# PCB_mezzanine_analog_template.net
KiCad netlist of a schematic drawn in Altium Designer
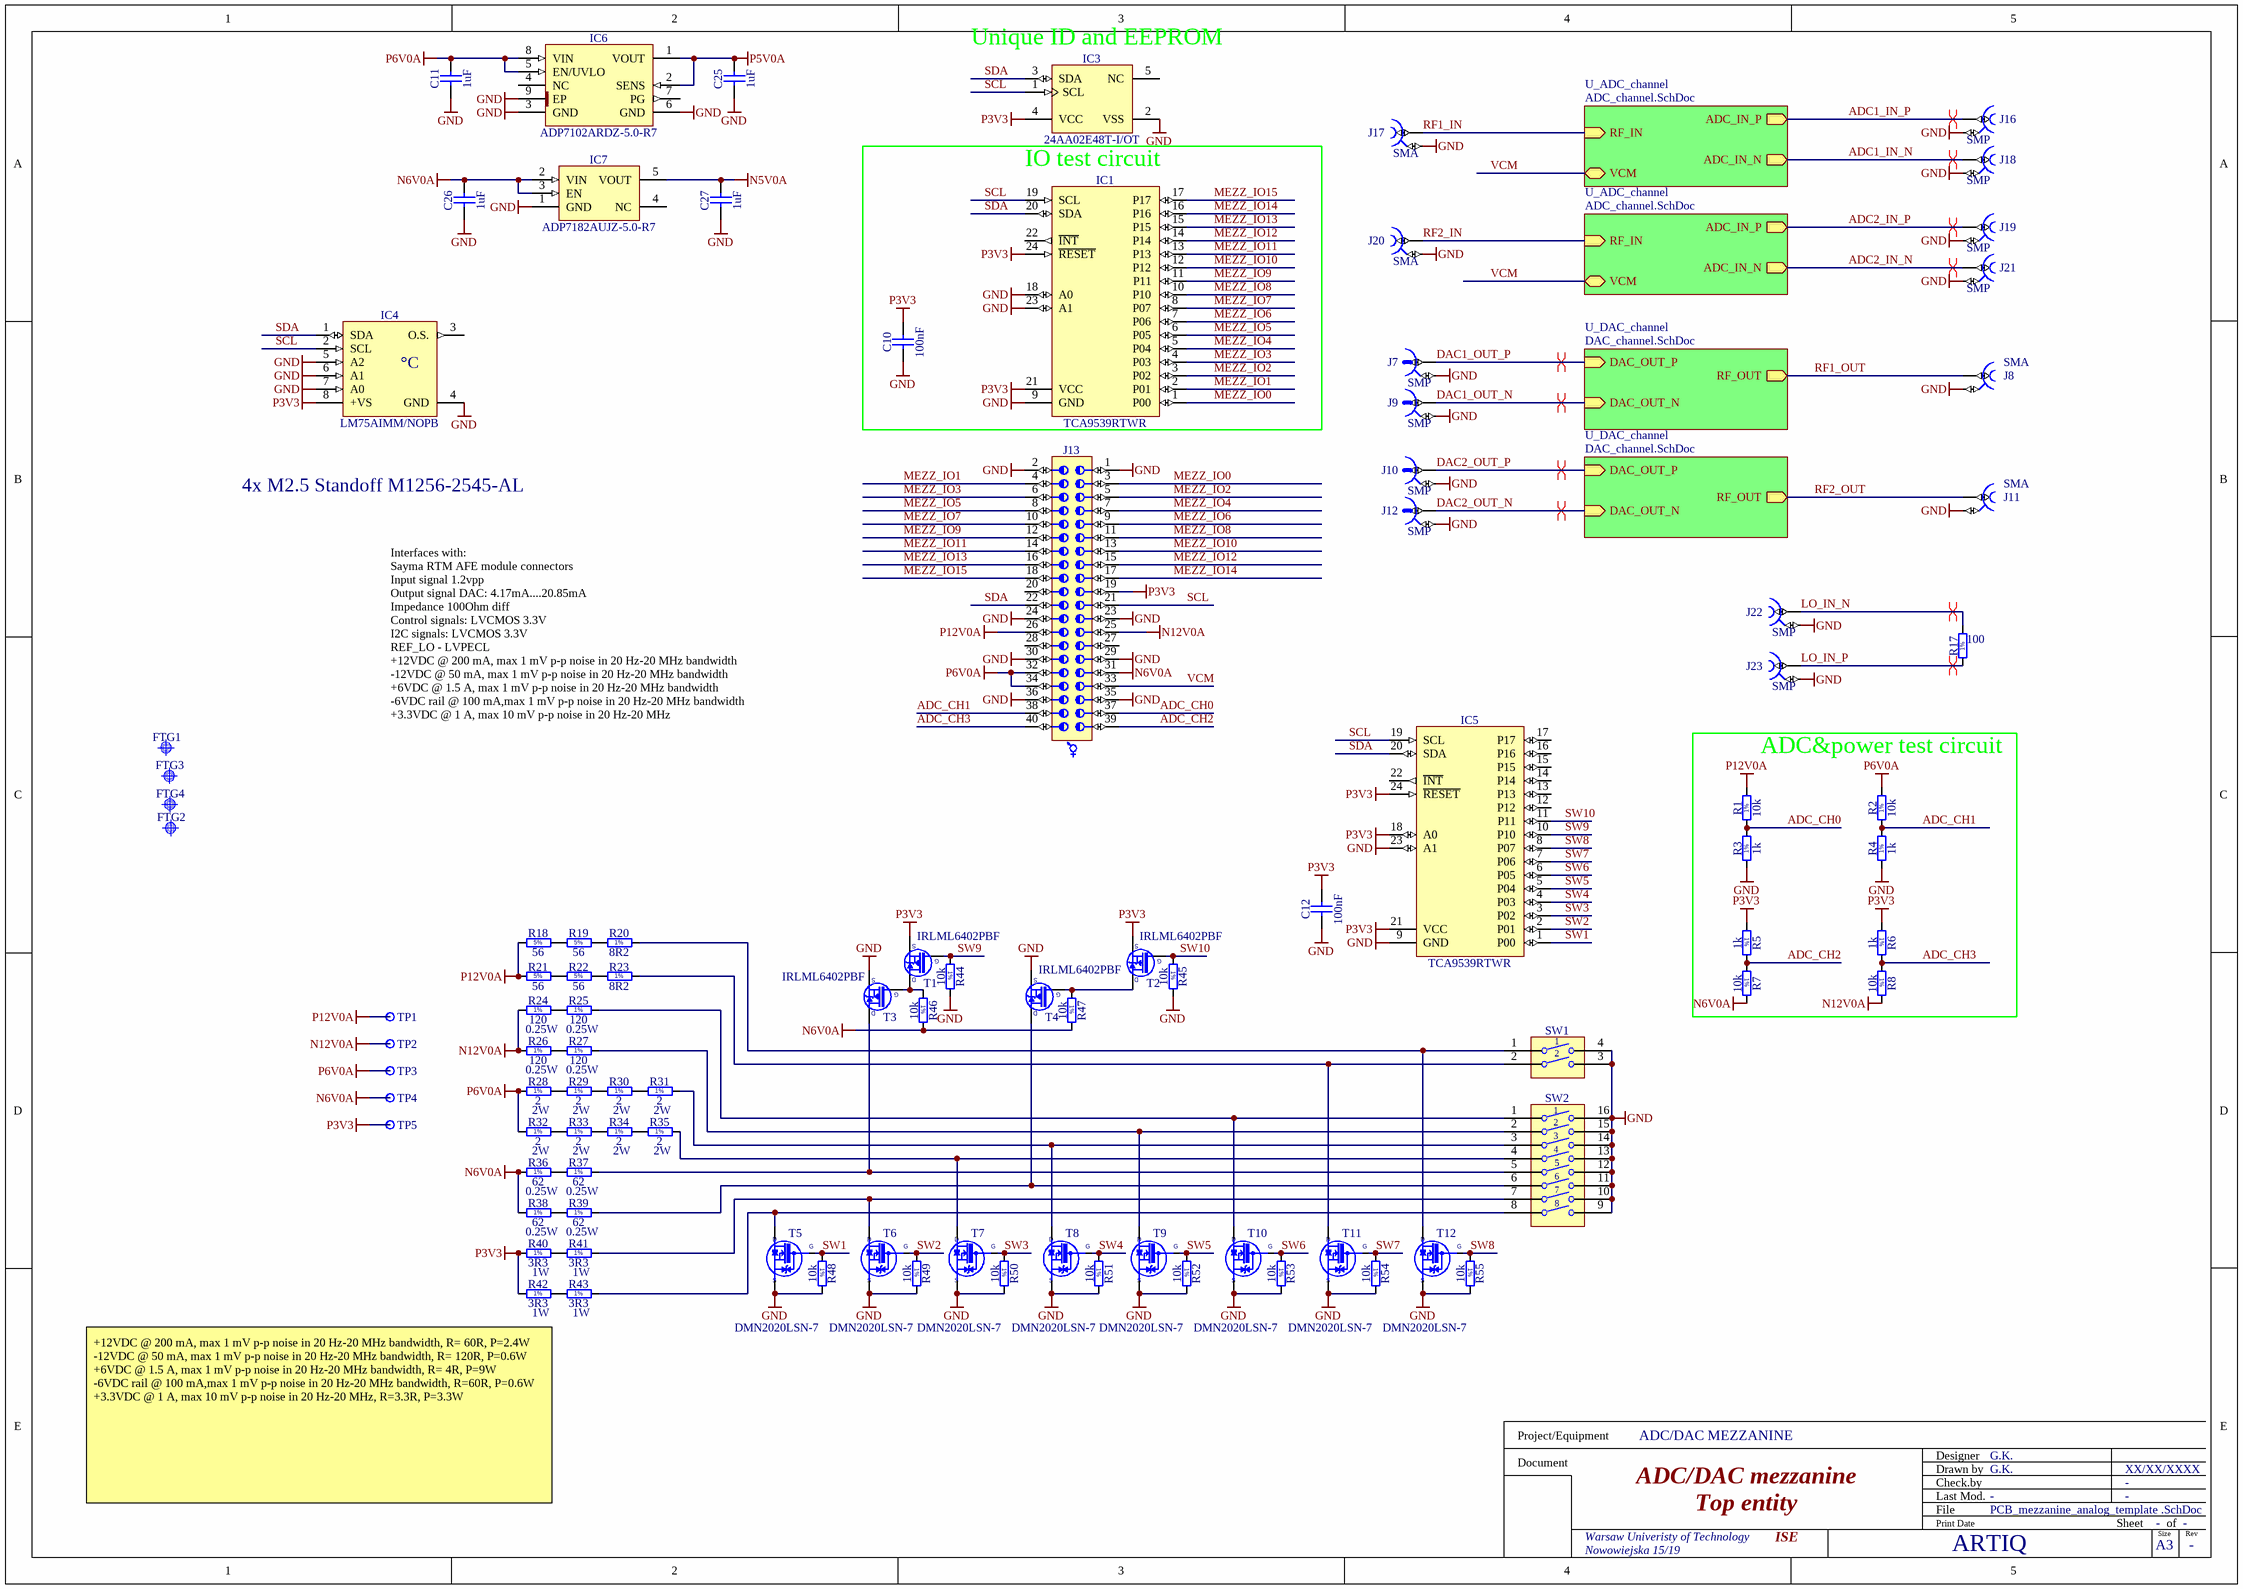
[diagram p0: PCB_mezzanine_analog_template .SchDoc]

(export (version "E")
  (design (tool "Eeschema 10.0.6"))
  (components
    (comp (ref "C10")
      (value "100nF")
      (footprint "CAPC1005X55N")
      (description "Non-polarised capacitor")
      (fields
        (field (name "PART NUMBER") "CC0402_100NF_16V_10%_X5R")
        (field (name "VOLTAGE") "16V")
        (field (name "AUTHOR") "CERN DEM JLC")
      )
      (libsource (lib "Capacitors") (part "Capacitor - non polarized"))
    )
    (comp (ref "C11")
      (value "1uF")
      (footprint "CAPC2012X140N")
      (description "Non-polarised capacitor")
      (fields
        (field (name "PART NUMBER") "CC0805_1UF_35V_20%_X7R")
        (field (name "VOLTAGE") "35V")
        (field (name "AUTHOR") "CERN DEM JLC")
      )
      (libsource (lib "Capacitors") (part "Capacitor - non polarized"))
    )
    (comp (ref "C12")
      (value "100nF")
      (footprint "CAPC1005X55N")
      (description "Non-polarised capacitor")
      (fields
        (field (name "PART NUMBER") "CC0402_100NF_16V_10%_X5R")
        (field (name "VOLTAGE") "16V")
        (field (name "AUTHOR") "CERN DEM JLC")
      )
      (libsource (lib "Capacitors") (part "Capacitor - non polarized"))
    )
    (comp (ref "C25")
      (value "1uF")
      (footprint "CAPC2012X140N")
      (description "Non-polarised capacitor")
      (fields
        (field (name "PART NUMBER") "CC0805_1UF_35V_20%_X7R")
        (field (name "VOLTAGE") "35V")
        (field (name "AUTHOR") "CERN DEM JLC")
      )
      (libsource (lib "Capacitors") (part "Capacitor - non polarized"))
    )
    (comp (ref "C26")
      (value "1uF")
      (footprint "CAPC2012X140N")
      (description "Non-polarised capacitor")
      (fields
        (field (name "PART NUMBER") "CC0805_1UF_35V_20%_X7R")
        (field (name "VOLTAGE") "35V")
        (field (name "AUTHOR") "CERN DEM JLC")
      )
      (libsource (lib "Capacitors") (part "Capacitor - non polarized"))
    )
    (comp (ref "C27")
      (value "1uF")
      (footprint "CAPC2012X140N")
      (description "Non-polarised capacitor")
      (fields
        (field (name "PART NUMBER") "CC0805_1UF_35V_20%_X7R")
        (field (name "VOLTAGE") "35V")
        (field (name "AUTHOR") "CERN DEM JLC")
      )
      (libsource (lib "Capacitors") (part "Capacitor - non polarized"))
    )
    (comp (ref "FTG1")
      (value "Use only in PCB")
      (footprint "FIDUCIAL_TOP_C100-200")
      (description "Fiducial Target")
      (fields (field (name "PART NUMBER") "FIDUCIAL_TARGET_C100-200") (field (name "AUTHOR") "CERN DEM JLC"))
      (libsource (lib "Eletro-mechanical") (part "Fiducial Target"))
    )
    (comp (ref "FTG2")
      (value "Use only in PCB")
      (footprint "FIDUCIAL_TOP_S100-200")
      (description "Fiducial Target")
      (fields (field (name "PART NUMBER") "FIDUCIAL_TARGET_S100-200") (field (name "AUTHOR") "CERN DEM JLC"))
      (libsource (lib "Eletro-mechanical") (part "Fiducial Target"))
    )
    (comp (ref "FTG3")
      (value "Use only in PCB")
      (footprint "FIDUCIAL_TOP_S100-200")
      (description "Fiducial Target")
      (fields (field (name "PART NUMBER") "FIDUCIAL_TARGET_S100-200") (field (name "AUTHOR") "CERN DEM JLC"))
      (libsource (lib "Eletro-mechanical") (part "Fiducial Target"))
    )
    (comp (ref "FTG4")
      (value "Use only in PCB")
      (footprint "FIDUCIAL_TOP_S200-400")
      (description "Fiducial Target")
      (fields (field (name "PART NUMBER") "FIDUCIAL_TARGET_S200-400") (field (name "AUTHOR") "CERN DEM JLC"))
      (libsource (lib "Eletro-mechanical") (part "Fiducial Target"))
    )
    (comp (ref "IC1")
      (value "TCA9539RTWR")
      (footprint "QFN50P400X400X80-25N-S255")
      (description "Low-Voltage 16-Bit I2C and SMBus I/O Expander")
      (fields (field (name "MANUFACTURER") "TEXAS INSTRUMENTS") (field (name "AUTHOR") "CERN DEM MR"))
      (libsource (lib "ICs And Semiconductors") (part "TCA9539RTWR"))
    )
    (comp (ref "IC3")
      (value "24AA02E48T-I/OT")
      (footprint "SOT95P280X145-5N")
      (description "1.7V-5.5V, 2K I2C Serial EEPROM With EUI-48 Node Identity")
      (fields (field (name "MANUFACTURER") "MICROCHIP TECHNOLOGY") (field (name "AUTHOR") "CERN DEM MR"))
      (libsource (lib "ICs And Semiconductors") (part "24AA02E48T-I/OT"))
    )
    (comp (ref "IC4")
      (value "LM75AIMM/NOPB")
      (footprint "SOP65P490X109-8N")
      (description "Digital Temperature Sensor and Thermal Watchdog with Two-Wire Interface")
      (fields (field (name "MANUFACTURER") "TEXAS INSTRUMENTS") (field (name "AUTHOR") "CERN DEM JLC"))
      (libsource (lib "ICs And Semiconductors") (part "LM75"))
    )
    (comp (ref "IC5")
      (value "TCA9539RTWR")
      (footprint "QFN50P400X400X80-25N-S255")
      (description "Low-Voltage 16-Bit I2C and SMBus I/O Expander")
      (fields (field (name "MANUFACTURER") "TEXAS INSTRUMENTS") (field (name "AUTHOR") "CERN DEM MR"))
      (libsource (lib "ICs And Semiconductors") (part "TCA9539RTWR"))
    )
    (comp (ref "IC6")
      (value "ADP7102ARDZ-5.0-R7")
      (footprint "SOIC127P600X175-9N-R241X309")
      (description "300 mA, Low Noise, CMOS LDO Linear Regulator")
      (fields (field (name "MANUFACTURER") "ANALOG DEVICES") (field (name "AUTHOR") "CERN DEM JLC"))
      (libsource (lib "ICs And Semiconductors") (part "ADP7102ARDZ-X.X-R7"))
    )
    (comp (ref "IC7")
      (value "ADP7182AUJZ-5.0-R7")
      (footprint "SOT95P280X90-5N")
      (description "–5V, 200 mA, Low Noise, Linear Regulator")
      (fields (field (name "MANUFACTURER") "ANALOG DEVICES") (field (name "AUTHOR") "CERN DEM JLC"))
      (libsource (lib "ICs And Semiconductors") (part "ADP7182AUJZ-X.X-R7"))
    )
    (comp (ref "J7")
      (value "SMP")
      (footprint "MOLEX_85305-0232")
      (fields
        (field (name "PART NUMBER") "MOLEX_85305-0232")
        (field (name "MANUFACTURER") "MOLEX")
        (field (name "MANUFACTURER PART NUMBER") "85305-0232")
        (field (name "AUTHOR") "CERN DEM JMW")
      )
      (libsource (lib "Connectors") (part "Coax_1Male_1Shield"))
    )
    (comp (ref "J8")
      (value "SMA")
      (footprint "TELEGARTNER_J01151A0451")
      (fields
        (field (name "PART NUMBER") "TELEGARTNER_J01151A0451")
        (field (name "MANUFACTURER") "TELEGARTNER")
        (field (name "MANUFACTURER PART NUMBER") "J01151A0451")
        (field (name "AUTHOR") "CERN DEM JLC")
      )
      (libsource (lib "") (part "Coax_1Female_1Shield_1"))
    )
    (comp (ref "J9")
      (value "SMP")
      (footprint "MOLEX_85305-0232")
      (fields
        (field (name "PART NUMBER") "MOLEX_85305-0232")
        (field (name "MANUFACTURER") "MOLEX")
        (field (name "MANUFACTURER PART NUMBER") "85305-0232")
        (field (name "AUTHOR") "CERN DEM JMW")
      )
      (libsource (lib "Connectors") (part "Coax_1Male_1Shield"))
    )
    (comp (ref "J10")
      (value "SMP")
      (footprint "MOLEX_85305-0232")
      (fields
        (field (name "PART NUMBER") "MOLEX_85305-0232")
        (field (name "MANUFACTURER") "MOLEX")
        (field (name "MANUFACTURER PART NUMBER") "85305-0232")
        (field (name "AUTHOR") "CERN DEM JMW")
      )
      (libsource (lib "Connectors") (part "Coax_1Male_1Shield"))
    )
    (comp (ref "J11")
      (value "SMA")
      (footprint "TELEGARTNER_J01151A0451")
      (fields
        (field (name "PART NUMBER") "TELEGARTNER_J01151A0451")
        (field (name "MANUFACTURER") "TELEGARTNER")
        (field (name "MANUFACTURER PART NUMBER") "J01151A0451")
        (field (name "AUTHOR") "CERN DEM JLC")
      )
      (libsource (lib "") (part "Coax_1Female_1Shield_1"))
    )
    (comp (ref "J12")
      (value "SMP")
      (footprint "MOLEX_85305-0232")
      (fields
        (field (name "PART NUMBER") "MOLEX_85305-0232")
        (field (name "MANUFACTURER") "MOLEX")
        (field (name "MANUFACTURER PART NUMBER") "85305-0232")
        (field (name "AUTHOR") "CERN DEM JMW")
      )
      (libsource (lib "Connectors") (part "Coax_1Male_1Shield"))
    )
    (comp (ref "J13")
      (value "~")
      (footprint "SAMTEC_LSS-120-03-L-DV-A")
      (description "Connector 40 Hermaphroditic")
      (fields
        (field (name "PART NUMBER") "SAMTEC_LSS-120-03-L-DV-A")
        (field (name "MANUFACTURER") "SAMTEC")
        (field (name "AUTHOR") "CERN DEM JMW")
      )
      (libsource (lib "Connectors") (part "Connector 40 Hermaphroditic"))
    )
    (comp (ref "J16")
      (value "SMP")
      (footprint "AMPHENOL_SMP-MSLD-PCT-10")
      (fields
        (field (name "PART NUMBER") "AMPHENOL_SMP-MSLD-PCT-10")
        (field (name "MANUFACTURER") "AMPHENOL")
        (field (name "MANUFACTURER PART NUMBER") "SMP-MSLD-PCT-10")
        (field (name "AUTHOR") "CERN DEM JLC")
      )
      (libsource (lib "") (part "Coax_1Female_1Shield_1"))
    )
    (comp (ref "J17")
      (value "SMA")
      (footprint "TELEGARTNER_J01151A0921")
      (fields
        (field (name "PART NUMBER") "TELEGARTNER_J01151A0921")
        (field (name "MANUFACTURER") "TELEGARTNER")
        (field (name "MANUFACTURER PART NUMBER") "J01151A0921")
        (field (name "AUTHOR") "CERN DEM JLC")
      )
      (libsource (lib "Connectors") (part "Coax_1Female_1Shield"))
    )
    (comp (ref "J18")
      (value "SMP")
      (footprint "AMPHENOL_SMP-MSLD-PCT-10")
      (fields
        (field (name "PART NUMBER") "AMPHENOL_SMP-MSLD-PCT-10")
        (field (name "MANUFACTURER") "AMPHENOL")
        (field (name "MANUFACTURER PART NUMBER") "SMP-MSLD-PCT-10")
        (field (name "AUTHOR") "CERN DEM JLC")
      )
      (libsource (lib "") (part "Coax_1Female_1Shield_1"))
    )
    (comp (ref "J19")
      (value "SMP")
      (footprint "AMPHENOL_SMP-MSLD-PCT-10")
      (fields
        (field (name "PART NUMBER") "AMPHENOL_SMP-MSLD-PCT-10")
        (field (name "MANUFACTURER") "AMPHENOL")
        (field (name "MANUFACTURER PART NUMBER") "SMP-MSLD-PCT-10")
        (field (name "AUTHOR") "CERN DEM JLC")
      )
      (libsource (lib "") (part "Coax_1Female_1Shield_1"))
    )
    (comp (ref "J20")
      (value "SMA")
      (footprint "TELEGARTNER_J01151A0921")
      (fields
        (field (name "PART NUMBER") "TELEGARTNER_J01151A0921")
        (field (name "MANUFACTURER") "TELEGARTNER")
        (field (name "MANUFACTURER PART NUMBER") "J01151A0921")
        (field (name "AUTHOR") "CERN DEM JLC")
      )
      (libsource (lib "Connectors") (part "Coax_1Female_1Shield"))
    )
    (comp (ref "J21")
      (value "SMP")
      (footprint "AMPHENOL_SMP-MSLD-PCT-10")
      (fields
        (field (name "PART NUMBER") "AMPHENOL_SMP-MSLD-PCT-10")
        (field (name "MANUFACTURER") "AMPHENOL")
        (field (name "MANUFACTURER PART NUMBER") "SMP-MSLD-PCT-10")
        (field (name "AUTHOR") "CERN DEM JLC")
      )
      (libsource (lib "") (part "Coax_1Female_1Shield_1"))
    )
    (comp (ref "J22")
      (value "SMP")
      (footprint "AMPHENOL_SMP-MSLD-PCT-10")
      (fields
        (field (name "PART NUMBER") "AMPHENOL_SMP-MSLD-PCT-10")
        (field (name "MANUFACTURER") "AMPHENOL")
        (field (name "MANUFACTURER PART NUMBER") "SMP-MSLD-PCT-10")
        (field (name "AUTHOR") "CERN DEM JLC")
      )
      (libsource (lib "Connectors") (part "Coax_1Female_1Shield"))
    )
    (comp (ref "J23")
      (value "SMP")
      (footprint "AMPHENOL_SMP-MSLD-PCT-10")
      (fields
        (field (name "PART NUMBER") "AMPHENOL_SMP-MSLD-PCT-10")
        (field (name "MANUFACTURER") "AMPHENOL")
        (field (name "MANUFACTURER PART NUMBER") "SMP-MSLD-PCT-10")
        (field (name "AUTHOR") "CERN DEM JLC")
      )
      (libsource (lib "Connectors") (part "Coax_1Female_1Shield"))
    )
    (comp (ref "R1")
      (value "10k")
      (footprint "RESC1005X40N")
      (description "Resistor - 1%")
      (fields
        (field (name "PART NUMBER") "R0402_10K_1%_0.0625W_100PPM")
        (field (name "POWER") "0.0625W")
        (field (name "AUTHOR") "CERN DEM JLC")
      )
      (libsource (lib "Resistors") (part "Resistor - 1%"))
    )
    (comp (ref "R2")
      (value "10k")
      (footprint "RESC1005X40N")
      (description "Resistor - 1%")
      (fields
        (field (name "PART NUMBER") "R0402_10K_1%_0.0625W_100PPM")
        (field (name "POWER") "0.0625W")
        (field (name "AUTHOR") "CERN DEM JLC")
      )
      (libsource (lib "Resistors") (part "Resistor - 1%"))
    )
    (comp (ref "R3")
      (value "1k")
      (footprint "RESC1005X40N")
      (description "Resistor - 1%")
      (fields
        (field (name "PART NUMBER") "R0402_1K_1%_0.0625W_100PPM")
        (field (name "POWER") "0.0625W")
        (field (name "AUTHOR") "CERN DEM JLC")
      )
      (libsource (lib "Resistors") (part "Resistor - 1%"))
    )
    (comp (ref "R4")
      (value "1k")
      (footprint "RESC1005X40N")
      (description "Resistor - 1%")
      (fields
        (field (name "PART NUMBER") "R0402_1K_1%_0.0625W_100PPM")
        (field (name "POWER") "0.0625W")
        (field (name "AUTHOR") "CERN DEM JLC")
      )
      (libsource (lib "Resistors") (part "Resistor - 1%"))
    )
    (comp (ref "R5")
      (value "1k")
      (footprint "RESC1005X40N")
      (description "Resistor - 1%")
      (fields
        (field (name "PART NUMBER") "R0402_1K_1%_0.0625W_100PPM")
        (field (name "POWER") "0.0625W")
        (field (name "AUTHOR") "CERN DEM JLC")
      )
      (libsource (lib "Resistors") (part "Resistor - 1%"))
    )
    (comp (ref "R6")
      (value "1k")
      (footprint "RESC1005X40N")
      (description "Resistor - 1%")
      (fields
        (field (name "PART NUMBER") "R0402_1K_1%_0.0625W_100PPM")
        (field (name "POWER") "0.0625W")
        (field (name "AUTHOR") "CERN DEM JLC")
      )
      (libsource (lib "Resistors") (part "Resistor - 1%"))
    )
    (comp (ref "R7")
      (value "10k")
      (footprint "RESC1005X40N")
      (description "Resistor - 1%")
      (fields
        (field (name "PART NUMBER") "R0402_10K_1%_0.0625W_100PPM")
        (field (name "POWER") "0.0625W")
        (field (name "AUTHOR") "CERN DEM JLC")
      )
      (libsource (lib "Resistors") (part "Resistor - 1%"))
    )
    (comp (ref "R8")
      (value "10k")
      (footprint "RESC1005X40N")
      (description "Resistor - 1%")
      (fields
        (field (name "PART NUMBER") "R0402_10K_1%_0.0625W_100PPM")
        (field (name "POWER") "0.0625W")
        (field (name "AUTHOR") "CERN DEM JLC")
      )
      (libsource (lib "Resistors") (part "Resistor - 1%"))
    )
    (comp (ref "R17")
      (value "100")
      (footprint "RESC1005X40N")
      (description "Resistor - 1%")
      (fields
        (field (name "PART NUMBER") "R0402_100R_1%_0.0625W_100PPM")
        (field (name "POWER") "0.0625W")
        (field (name "AUTHOR") "CERN DEM JLC")
      )
      (libsource (lib "Resistors") (part "Resistor - 1%"))
    )
    (comp (ref "R18")
      (value "56")
      (footprint "RESC6331X70N")
      (description "Resistor - 5%")
      (fields
        (field (name "PART NUMBER") "R2512_56R_5%_1W_200PPM")
        (field (name "POWER") "1W")
        (field (name "AUTHOR") "CERN DEM JLC")
      )
      (libsource (lib "Resistors") (part "Resistor - 5%"))
    )
    (comp (ref "R19")
      (value "56")
      (footprint "RESC6331X70N")
      (description "Resistor - 5%")
      (fields
        (field (name "PART NUMBER") "R2512_56R_5%_1W_200PPM")
        (field (name "POWER") "1W")
        (field (name "AUTHOR") "CERN DEM JLC")
      )
      (libsource (lib "Resistors") (part "Resistor - 5%"))
    )
    (comp (ref "R20")
      (value "8R2")
      (footprint "RESC3216X65N")
      (description "Resistor - 1%")
      (fields
        (field (name "PART NUMBER") "R1206_8R2_1%_0.25W_200PPM")
        (field (name "POWER") "0.25W")
        (field (name "AUTHOR") "CERN DEM JLC")
      )
      (libsource (lib "Resistors") (part "Resistor - 1%"))
    )
    (comp (ref "R21")
      (value "56")
      (footprint "RESC6331X70N")
      (description "Resistor - 5%")
      (fields
        (field (name "PART NUMBER") "R2512_56R_5%_1W_200PPM")
        (field (name "POWER") "1W")
        (field (name "AUTHOR") "CERN DEM JLC")
      )
      (libsource (lib "Resistors") (part "Resistor - 5%"))
    )
    (comp (ref "R22")
      (value "56")
      (footprint "RESC6331X70N")
      (description "Resistor - 5%")
      (fields
        (field (name "PART NUMBER") "R2512_56R_5%_1W_200PPM")
        (field (name "POWER") "1W")
        (field (name "AUTHOR") "CERN DEM JLC")
      )
      (libsource (lib "Resistors") (part "Resistor - 5%"))
    )
    (comp (ref "R23")
      (value "8R2")
      (footprint "RESC3216X65N")
      (description "Resistor - 1%")
      (fields
        (field (name "PART NUMBER") "R1206_8R2_1%_0.25W_200PPM")
        (field (name "POWER") "0.25W")
        (field (name "AUTHOR") "CERN DEM JLC")
      )
      (libsource (lib "Resistors") (part "Resistor - 1%"))
    )
    (comp (ref "R24")
      (value "120")
      (footprint "RESC3216X65N")
      (description "Resistor - 1%")
      (fields
        (field (name "PART NUMBER") "R1206_120R_1%_0.25W_100PPM")
        (field (name "POWER") "0.25W")
        (field (name "TOLERANCE") "±1%")
        (field (name "AUTHOR") "CERN DEM JLC")
      )
      (libsource (lib "Resistors") (part "Resistor - 1%"))
    )
    (comp (ref "R25")
      (value "120")
      (footprint "RESC3216X65N")
      (description "Resistor - 1%")
      (fields
        (field (name "PART NUMBER") "R1206_120R_1%_0.25W_100PPM")
        (field (name "POWER") "0.25W")
        (field (name "TOLERANCE") "±1%")
        (field (name "AUTHOR") "CERN DEM JLC")
      )
      (libsource (lib "Resistors") (part "Resistor - 1%"))
    )
    (comp (ref "R26")
      (value "120")
      (footprint "RESC3216X65N")
      (description "Resistor - 1%")
      (fields
        (field (name "PART NUMBER") "R1206_120R_1%_0.25W_100PPM")
        (field (name "POWER") "0.25W")
        (field (name "TOLERANCE") "±1%")
        (field (name "AUTHOR") "CERN DEM JLC")
      )
      (libsource (lib "Resistors") (part "Resistor - 1%"))
    )
    (comp (ref "R27")
      (value "120")
      (footprint "RESC3216X65N")
      (description "Resistor - 1%")
      (fields
        (field (name "PART NUMBER") "R1206_120R_1%_0.25W_100PPM")
        (field (name "POWER") "0.25W")
        (field (name "TOLERANCE") "±1%")
        (field (name "AUTHOR") "CERN DEM JLC")
      )
      (libsource (lib "Resistors") (part "Resistor - 1%"))
    )
    (comp (ref "R28")
      (value "2")
      (footprint "RESM11670X449N")
      (description "Resistor - 1%")
      (fields
        (field (name "PART NUMBER") "R4527_2R_1%_2W_50PPM")
        (field (name "POWER") "2W")
        (field (name "TOLERANCE") "±1%")
        (field (name "AUTHOR") "CERN DEM JLC")
      )
      (libsource (lib "Resistors") (part "Resistor - 1%"))
    )
    (comp (ref "R29")
      (value "2")
      (footprint "RESM11670X449N")
      (description "Resistor - 1%")
      (fields
        (field (name "PART NUMBER") "R4527_2R_1%_2W_50PPM")
        (field (name "POWER") "2W")
        (field (name "TOLERANCE") "±1%")
        (field (name "AUTHOR") "CERN DEM JLC")
      )
      (libsource (lib "Resistors") (part "Resistor - 1%"))
    )
    (comp (ref "R30")
      (value "2")
      (footprint "RESM11670X449N")
      (description "Resistor - 1%")
      (fields
        (field (name "PART NUMBER") "R4527_2R_1%_2W_50PPM")
        (field (name "POWER") "2W")
        (field (name "TOLERANCE") "±1%")
        (field (name "AUTHOR") "CERN DEM JLC")
      )
      (libsource (lib "Resistors") (part "Resistor - 1%"))
    )
    (comp (ref "R31")
      (value "2")
      (footprint "RESM11670X449N")
      (description "Resistor - 1%")
      (fields
        (field (name "PART NUMBER") "R4527_2R_1%_2W_50PPM")
        (field (name "POWER") "2W")
        (field (name "TOLERANCE") "±1%")
        (field (name "AUTHOR") "CERN DEM JLC")
      )
      (libsource (lib "Resistors") (part "Resistor - 1%"))
    )
    (comp (ref "R32")
      (value "2")
      (footprint "RESM11670X449N")
      (description "Resistor - 1%")
      (fields
        (field (name "PART NUMBER") "R4527_2R_1%_2W_50PPM")
        (field (name "POWER") "2W")
        (field (name "TOLERANCE") "±1%")
        (field (name "AUTHOR") "CERN DEM JLC")
      )
      (libsource (lib "Resistors") (part "Resistor - 1%"))
    )
    (comp (ref "R33")
      (value "2")
      (footprint "RESM11670X449N")
      (description "Resistor - 1%")
      (fields
        (field (name "PART NUMBER") "R4527_2R_1%_2W_50PPM")
        (field (name "POWER") "2W")
        (field (name "TOLERANCE") "±1%")
        (field (name "AUTHOR") "CERN DEM JLC")
      )
      (libsource (lib "Resistors") (part "Resistor - 1%"))
    )
    (comp (ref "R34")
      (value "2")
      (footprint "RESM11670X449N")
      (description "Resistor - 1%")
      (fields
        (field (name "PART NUMBER") "R4527_2R_1%_2W_50PPM")
        (field (name "POWER") "2W")
        (field (name "TOLERANCE") "±1%")
        (field (name "AUTHOR") "CERN DEM JLC")
      )
      (libsource (lib "Resistors") (part "Resistor - 1%"))
    )
    (comp (ref "R35")
      (value "2")
      (footprint "RESM11670X449N")
      (description "Resistor - 1%")
      (fields
        (field (name "PART NUMBER") "R4527_2R_1%_2W_50PPM")
        (field (name "POWER") "2W")
        (field (name "TOLERANCE") "±1%")
        (field (name "AUTHOR") "CERN DEM JLC")
      )
      (libsource (lib "Resistors") (part "Resistor - 1%"))
    )
    (comp (ref "R36")
      (value "62")
      (footprint "RESC3216X65N")
      (description "Resistor - 1%")
      (fields
        (field (name "PART NUMBER") "R1206_62R_1%_0.25W_100PPM")
        (field (name "POWER") "0.25W")
        (field (name "TOLERANCE") "±1%")
        (field (name "AUTHOR") "CERN DEM JLC")
      )
      (libsource (lib "Resistors") (part "Resistor - 1%"))
    )
    (comp (ref "R37")
      (value "62")
      (footprint "RESC3216X65N")
      (description "Resistor - 1%")
      (fields
        (field (name "PART NUMBER") "R1206_62R_1%_0.25W_100PPM")
        (field (name "POWER") "0.25W")
        (field (name "TOLERANCE") "±1%")
        (field (name "AUTHOR") "CERN DEM JLC")
      )
      (libsource (lib "Resistors") (part "Resistor - 1%"))
    )
    (comp (ref "R38")
      (value "62")
      (footprint "RESC3216X65N")
      (description "Resistor - 1%")
      (fields
        (field (name "PART NUMBER") "R1206_62R_1%_0.25W_100PPM")
        (field (name "POWER") "0.25W")
        (field (name "TOLERANCE") "±1%")
        (field (name "AUTHOR") "CERN DEM JLC")
      )
      (libsource (lib "Resistors") (part "Resistor - 1%"))
    )
    (comp (ref "R39")
      (value "62")
      (footprint "RESC3216X65N")
      (description "Resistor - 1%")
      (fields
        (field (name "PART NUMBER") "R1206_62R_1%_0.25W_100PPM")
        (field (name "POWER") "0.25W")
        (field (name "TOLERANCE") "±1%")
        (field (name "AUTHOR") "CERN DEM JLC")
      )
      (libsource (lib "Resistors") (part "Resistor - 1%"))
    )
    (comp (ref "R40")
      (value "3R3")
      (footprint "RESC6331X70N")
      (description "Resistor - 1%")
      (fields
        (field (name "PART NUMBER") "R2512_3R3_1%_1W_200PPM")
        (field (name "POWER") "1W")
        (field (name "TOLERANCE") "±1%")
        (field (name "AUTHOR") "CERN DEM JLC")
      )
      (libsource (lib "Resistors") (part "Resistor - 1%"))
    )
    (comp (ref "R41")
      (value "3R3")
      (footprint "RESC6331X70N")
      (description "Resistor - 1%")
      (fields
        (field (name "PART NUMBER") "R2512_3R3_1%_1W_200PPM")
        (field (name "POWER") "1W")
        (field (name "TOLERANCE") "±1%")
        (field (name "AUTHOR") "CERN DEM JLC")
      )
      (libsource (lib "Resistors") (part "Resistor - 1%"))
    )
    (comp (ref "R42")
      (value "3R3")
      (footprint "RESC6331X70N")
      (description "Resistor - 1%")
      (fields
        (field (name "PART NUMBER") "R2512_3R3_1%_1W_200PPM")
        (field (name "POWER") "1W")
        (field (name "TOLERANCE") "±1%")
        (field (name "AUTHOR") "CERN DEM JLC")
      )
      (libsource (lib "Resistors") (part "Resistor - 1%"))
    )
    (comp (ref "R43")
      (value "3R3")
      (footprint "RESC6331X70N")
      (description "Resistor - 1%")
      (fields
        (field (name "PART NUMBER") "R2512_3R3_1%_1W_200PPM")
        (field (name "POWER") "1W")
        (field (name "TOLERANCE") "±1%")
        (field (name "AUTHOR") "CERN DEM JLC")
      )
      (libsource (lib "Resistors") (part "Resistor - 1%"))
    )
    (comp (ref "R44")
      (value "10k")
      (footprint "RESC1005X40N")
      (description "Resistor - 1%")
      (fields
        (field (name "PART NUMBER") "R0402_10K_1%_0.0625W_100PPM")
        (field (name "POWER") "0.0625W")
        (field (name "AUTHOR") "CERN DEM JLC")
      )
      (libsource (lib "Resistors") (part "Resistor - 1%"))
    )
    (comp (ref "R45")
      (value "10k")
      (footprint "RESC1005X40N")
      (description "Resistor - 1%")
      (fields
        (field (name "PART NUMBER") "R0402_10K_1%_0.0625W_100PPM")
        (field (name "POWER") "0.0625W")
        (field (name "AUTHOR") "CERN DEM JLC")
      )
      (libsource (lib "Resistors") (part "Resistor - 1%"))
    )
    (comp (ref "R46")
      (value "10k")
      (footprint "RESC1005X40N")
      (description "Resistor - 1%")
      (fields
        (field (name "PART NUMBER") "R0402_10K_1%_0.0625W_100PPM")
        (field (name "POWER") "0.0625W")
        (field (name "AUTHOR") "CERN DEM JLC")
      )
      (libsource (lib "Resistors") (part "Resistor - 1%"))
    )
    (comp (ref "R47")
      (value "10k")
      (footprint "RESC1005X40N")
      (description "Resistor - 1%")
      (fields
        (field (name "PART NUMBER") "R0402_10K_1%_0.0625W_100PPM")
        (field (name "POWER") "0.0625W")
        (field (name "AUTHOR") "CERN DEM JLC")
      )
      (libsource (lib "Resistors") (part "Resistor - 1%"))
    )
    (comp (ref "R48")
      (value "10k")
      (footprint "RESC1005X40N")
      (description "Resistor - 1%")
      (fields
        (field (name "PART NUMBER") "R0402_10K_1%_0.0625W_100PPM")
        (field (name "POWER") "0.0625W")
        (field (name "AUTHOR") "CERN DEM JLC")
      )
      (libsource (lib "Resistors") (part "Resistor - 1%"))
    )
    (comp (ref "R49")
      (value "10k")
      (footprint "RESC1005X40N")
      (description "Resistor - 1%")
      (fields
        (field (name "PART NUMBER") "R0402_10K_1%_0.0625W_100PPM")
        (field (name "POWER") "0.0625W")
        (field (name "AUTHOR") "CERN DEM JLC")
      )
      (libsource (lib "Resistors") (part "Resistor - 1%"))
    )
    (comp (ref "R50")
      (value "10k")
      (footprint "RESC1005X40N")
      (description "Resistor - 1%")
      (fields
        (field (name "PART NUMBER") "R0402_10K_1%_0.0625W_100PPM")
        (field (name "POWER") "0.0625W")
        (field (name "AUTHOR") "CERN DEM JLC")
      )
      (libsource (lib "Resistors") (part "Resistor - 1%"))
    )
    (comp (ref "R51")
      (value "10k")
      (footprint "RESC1005X40N")
      (description "Resistor - 1%")
      (fields
        (field (name "PART NUMBER") "R0402_10K_1%_0.0625W_100PPM")
        (field (name "POWER") "0.0625W")
        (field (name "AUTHOR") "CERN DEM JLC")
      )
      (libsource (lib "Resistors") (part "Resistor - 1%"))
    )
    (comp (ref "R52")
      (value "10k")
      (footprint "RESC1005X40N")
      (description "Resistor - 1%")
      (fields
        (field (name "PART NUMBER") "R0402_10K_1%_0.0625W_100PPM")
        (field (name "POWER") "0.0625W")
        (field (name "AUTHOR") "CERN DEM JLC")
      )
      (libsource (lib "Resistors") (part "Resistor - 1%"))
    )
    (comp (ref "R53")
      (value "10k")
      (footprint "RESC1005X40N")
      (description "Resistor - 1%")
      (fields
        (field (name "PART NUMBER") "R0402_10K_1%_0.0625W_100PPM")
        (field (name "POWER") "0.0625W")
        (field (name "AUTHOR") "CERN DEM JLC")
      )
      (libsource (lib "Resistors") (part "Resistor - 1%"))
    )
    (comp (ref "R54")
      (value "10k")
      (footprint "RESC1005X40N")
      (description "Resistor - 1%")
      (fields
        (field (name "PART NUMBER") "R0402_10K_1%_0.0625W_100PPM")
        (field (name "POWER") "0.0625W")
        (field (name "AUTHOR") "CERN DEM JLC")
      )
      (libsource (lib "Resistors") (part "Resistor - 1%"))
    )
    (comp (ref "R55")
      (value "10k")
      (footprint "RESC1005X40N")
      (description "Resistor - 1%")
      (fields
        (field (name "PART NUMBER") "R0402_10K_1%_0.0625W_100PPM")
        (field (name "POWER") "0.0625W")
        (field (name "AUTHOR") "CERN DEM JLC")
      )
      (libsource (lib "Resistors") (part "Resistor - 1%"))
    )
    (comp (ref "SW1")
      (value "Switch")
      (footprint "SW_OMRON_A6S-2102-H")
      (description "2 Ways SPST DIP Switch")
      (fields
        (field (name "PART NUMBER") "SW_OMRON_A6S-2102-H")
        (field (name "MANUFACTURER") "OMRON")
        (field (name "AUTHOR") "CERN DEM JMW")
      )
      (libsource (lib "Eletro-mechanical") (part "SW 2x SPST DIP Switch"))
    )
    (comp (ref "SW2")
      (value "Switch")
      (footprint "SW_OMRON_A6S-8102-H")
      (description "8 Ways SPST DIP Switch")
      (fields
        (field (name "PART NUMBER") "SW_OMRON_A6S-8102-H")
        (field (name "MANUFACTURER") "OMRON")
        (field (name "AUTHOR") "CERN DEM JMW")
      )
      (libsource (lib "Eletro-mechanical") (part "SW 8x SPST DIP Switch"))
    )
    (comp (ref "T1")
      (value "IRLML6402PBF")
      (footprint "SOT95P237X112-3N")
      (description "P-CHANNEL MOSFET WITH ZENER DIODE")
      (fields (field (name "MANUFACTURER") "INTERNATIONAL RECTIFIER") (field (name "AUTHOR") "CERN DEM JLC"))
      (libsource (lib "ICs And Semiconductors") (part "P-MOSFET-DZ 1G 2S 3D"))
    )
    (comp (ref "T2")
      (value "IRLML6402PBF")
      (footprint "SOT95P237X112-3N")
      (description "P-CHANNEL MOSFET WITH ZENER DIODE")
      (fields (field (name "MANUFACTURER") "INTERNATIONAL RECTIFIER") (field (name "AUTHOR") "CERN DEM JLC"))
      (libsource (lib "ICs And Semiconductors") (part "P-MOSFET-DZ 1G 2S 3D"))
    )
    (comp (ref "T3")
      (value "IRLML6402PBF")
      (footprint "SOT95P237X112-3N")
      (description "P-CHANNEL MOSFET WITH ZENER DIODE")
      (fields (field (name "MANUFACTURER") "INTERNATIONAL RECTIFIER") (field (name "AUTHOR") "CERN DEM JLC"))
      (libsource (lib "ICs And Semiconductors") (part "P-MOSFET-DZ 1G 2S 3D"))
    )
    (comp (ref "T4")
      (value "IRLML6402PBF")
      (footprint "SOT95P237X112-3N")
      (description "P-CHANNEL MOSFET WITH ZENER DIODE")
      (fields (field (name "MANUFACTURER") "INTERNATIONAL RECTIFIER") (field (name "AUTHOR") "CERN DEM JLC"))
      (libsource (lib "ICs And Semiconductors") (part "P-MOSFET-DZ 1G 2S 3D"))
    )
    (comp (ref "T5")
      (value "DMN2020LSN-7")
      (footprint "SOT95P285X140-3N")
      (description "20V, 6.9A, N-Channel Enhancement Mode MOSFET")
      (fields (field (name "MANUFACTURER") "DIODES INCORPORATED") (field (name "AUTHOR") "CERN DEM JLC"))
      (libsource (lib "ICs And Semiconductors") (part "DMN2020LSN-7"))
    )
    (comp (ref "T6")
      (value "DMN2020LSN-7")
      (footprint "SOT95P285X140-3N")
      (description "20V, 6.9A, N-Channel Enhancement Mode MOSFET")
      (fields (field (name "MANUFACTURER") "DIODES INCORPORATED") (field (name "AUTHOR") "CERN DEM JLC"))
      (libsource (lib "ICs And Semiconductors") (part "DMN2020LSN-7"))
    )
    (comp (ref "T7")
      (value "DMN2020LSN-7")
      (footprint "SOT95P285X140-3N")
      (description "20V, 6.9A, N-Channel Enhancement Mode MOSFET")
      (fields (field (name "MANUFACTURER") "DIODES INCORPORATED") (field (name "AUTHOR") "CERN DEM JLC"))
      (libsource (lib "ICs And Semiconductors") (part "DMN2020LSN-7"))
    )
    (comp (ref "T8")
      (value "DMN2020LSN-7")
      (footprint "SOT95P285X140-3N")
      (description "20V, 6.9A, N-Channel Enhancement Mode MOSFET")
      (fields (field (name "MANUFACTURER") "DIODES INCORPORATED") (field (name "AUTHOR") "CERN DEM JLC"))
      (libsource (lib "ICs And Semiconductors") (part "DMN2020LSN-7"))
    )
    (comp (ref "T9")
      (value "DMN2020LSN-7")
      (footprint "SOT95P285X140-3N")
      (description "20V, 6.9A, N-Channel Enhancement Mode MOSFET")
      (fields (field (name "MANUFACTURER") "DIODES INCORPORATED") (field (name "AUTHOR") "CERN DEM JLC"))
      (libsource (lib "ICs And Semiconductors") (part "DMN2020LSN-7"))
    )
    (comp (ref "T10")
      (value "DMN2020LSN-7")
      (footprint "SOT95P285X140-3N")
      (description "20V, 6.9A, N-Channel Enhancement Mode MOSFET")
      (fields (field (name "MANUFACTURER") "DIODES INCORPORATED") (field (name "AUTHOR") "CERN DEM JLC"))
      (libsource (lib "ICs And Semiconductors") (part "DMN2020LSN-7"))
    )
    (comp (ref "T11")
      (value "DMN2020LSN-7")
      (footprint "SOT95P285X140-3N")
      (description "20V, 6.9A, N-Channel Enhancement Mode MOSFET")
      (fields (field (name "MANUFACTURER") "DIODES INCORPORATED") (field (name "AUTHOR") "CERN DEM JLC"))
      (libsource (lib "ICs And Semiconductors") (part "DMN2020LSN-7"))
    )
    (comp (ref "T12")
      (value "DMN2020LSN-7")
      (footprint "SOT95P285X140-3N")
      (description "20V, 6.9A, N-Channel Enhancement Mode MOSFET")
      (fields (field (name "MANUFACTURER") "DIODES INCORPORATED") (field (name "AUTHOR") "CERN DEM JLC"))
      (libsource (lib "ICs And Semiconductors") (part "DMN2020LSN-7"))
    )
    (comp (ref "TP1")
      (value "Test Point")
      (footprint "TPS127")
      (fields (field (name "PART NUMBER") "SMD_PAD_1.27X1.27MM") (field (name "AUTHOR") "CERN DEM JLC"))
      (libsource (lib "Eletro-mechanical") (part "Test Point"))
    )
    (comp (ref "TP2")
      (value "Test Point")
      (footprint "TPS127")
      (fields (field (name "PART NUMBER") "SMD_PAD_1.27X1.27MM") (field (name "AUTHOR") "CERN DEM JLC"))
      (libsource (lib "Eletro-mechanical") (part "Test Point"))
    )
    (comp (ref "TP3")
      (value "Test Point")
      (footprint "TPS127")
      (fields (field (name "PART NUMBER") "SMD_PAD_1.27X1.27MM") (field (name "AUTHOR") "CERN DEM JLC"))
      (libsource (lib "Eletro-mechanical") (part "Test Point"))
    )
    (comp (ref "TP4")
      (value "Test Point")
      (footprint "TPS127")
      (fields (field (name "PART NUMBER") "SMD_PAD_1.27X1.27MM") (field (name "AUTHOR") "CERN DEM JLC"))
      (libsource (lib "Eletro-mechanical") (part "Test Point"))
    )
    (comp (ref "TP5")
      (value "Test Point")
      (footprint "TPS127")
      (fields (field (name "PART NUMBER") "SMD_PAD_1.27X1.27MM") (field (name "AUTHOR") "CERN DEM JLC"))
      (libsource (lib "Eletro-mechanical") (part "Test Point"))
    )
  )
  (nets
    (net (code "1") (name "/ADC1_IN_N") (class "Default")
      (node (ref "J18") (pin "1") (pinfunction "1_1") (pintype "bidirectional"))
    )
    (net (code "2") (name "/ADC1_IN_P") (class "Default")
      (node (ref "J16") (pin "1") (pinfunction "1_1") (pintype "bidirectional"))
    )
    (net (code "3") (name "/ADC2_IN_N") (class "Default")
      (node (ref "J21") (pin "1") (pinfunction "1_1") (pintype "bidirectional"))
    )
    (net (code "4") (name "/ADC2_IN_P") (class "Default")
      (node (ref "J19") (pin "1") (pinfunction "1_1") (pintype "bidirectional"))
    )
    (net (code "5") (name "/ADC_CH0") (class "Default")
      (node (ref "J13") (pin "37") (pinfunction "37_37") (pintype "bidirectional"))
      (node (ref "R1") (pin "1") (pinfunction "1_1") (pintype "passive"))
      (node (ref "R3") (pin "2") (pinfunction "2_2") (pintype "passive"))
    )
    (net (code "6") (name "/ADC_CH1") (class "Default")
      (node (ref "J13") (pin "38") (pinfunction "38_38") (pintype "bidirectional"))
      (node (ref "R2") (pin "1") (pinfunction "1_1") (pintype "passive"))
      (node (ref "R4") (pin "2") (pinfunction "2_2") (pintype "passive"))
    )
    (net (code "7") (name "/ADC_CH2") (class "Default")
      (node (ref "J13") (pin "39") (pinfunction "39_39") (pintype "bidirectional"))
      (node (ref "R5") (pin "2") (pinfunction "2_2") (pintype "passive"))
      (node (ref "R7") (pin "1") (pinfunction "1_1") (pintype "passive"))
    )
    (net (code "8") (name "/ADC_CH3") (class "Default")
      (node (ref "J13") (pin "40") (pinfunction "40_40") (pintype "bidirectional"))
      (node (ref "R6") (pin "2") (pinfunction "2_2") (pintype "passive"))
      (node (ref "R8") (pin "1") (pinfunction "1_1") (pintype "passive"))
    )
    (net (code "9") (name "/DAC1_OUT_N") (class "Default")
      (node (ref "J9") (pin "1") (pinfunction "1_1") (pintype "bidirectional"))
    )
    (net (code "10") (name "/DAC1_OUT_P") (class "Default")
      (node (ref "J7") (pin "1") (pinfunction "1_1") (pintype "bidirectional"))
    )
    (net (code "11") (name "/DAC2_OUT_N") (class "Default")
      (node (ref "J12") (pin "1") (pinfunction "1_1") (pintype "bidirectional"))
    )
    (net (code "12") (name "/DAC2_OUT_P") (class "Default")
      (node (ref "J10") (pin "1") (pinfunction "1_1") (pintype "bidirectional"))
    )
    (net (code "13") (name "/LO_IN_N") (class "Default")
      (node (ref "J22") (pin "1") (pinfunction "1_1") (pintype "bidirectional"))
      (node (ref "R17") (pin "2") (pinfunction "2_2") (pintype "passive"))
    )
    (net (code "14") (name "/LO_IN_P") (class "Default")
      (node (ref "J23") (pin "1") (pinfunction "1_1") (pintype "bidirectional"))
      (node (ref "R17") (pin "1") (pinfunction "1_1") (pintype "passive"))
    )
    (net (code "15") (name "/MEZZ_IO0") (class "Default")
      (node (ref "IC1") (pin "1") (pinfunction "P00_1") (pintype "bidirectional"))
      (node (ref "J13") (pin "3") (pinfunction "3_3") (pintype "bidirectional"))
    )
    (net (code "16") (name "/MEZZ_IO1") (class "Default")
      (node (ref "IC1") (pin "2") (pinfunction "P01_2") (pintype "bidirectional"))
      (node (ref "J13") (pin "4") (pinfunction "4_4") (pintype "bidirectional"))
    )
    (net (code "17") (name "/MEZZ_IO2") (class "Default")
      (node (ref "IC1") (pin "3") (pinfunction "P02_3") (pintype "bidirectional"))
      (node (ref "J13") (pin "5") (pinfunction "5_5") (pintype "bidirectional"))
    )
    (net (code "18") (name "/MEZZ_IO3") (class "Default")
      (node (ref "IC1") (pin "4") (pinfunction "P03_4") (pintype "bidirectional"))
      (node (ref "J13") (pin "6") (pinfunction "6_6") (pintype "bidirectional"))
    )
    (net (code "19") (name "/MEZZ_IO4") (class "Default")
      (node (ref "IC1") (pin "5") (pinfunction "P04_5") (pintype "bidirectional"))
      (node (ref "J13") (pin "7") (pinfunction "7_7") (pintype "bidirectional"))
    )
    (net (code "20") (name "/MEZZ_IO5") (class "Default")
      (node (ref "IC1") (pin "6") (pinfunction "P05_6") (pintype "bidirectional"))
      (node (ref "J13") (pin "8") (pinfunction "8_8") (pintype "bidirectional"))
    )
    (net (code "21") (name "/MEZZ_IO6") (class "Default")
      (node (ref "IC1") (pin "7") (pinfunction "P06_7") (pintype "bidirectional"))
      (node (ref "J13") (pin "9") (pinfunction "9_9") (pintype "bidirectional"))
    )
    (net (code "22") (name "/MEZZ_IO7") (class "Default")
      (node (ref "IC1") (pin "8") (pinfunction "P07_8") (pintype "bidirectional"))
      (node (ref "J13") (pin "10") (pinfunction "10_10") (pintype "bidirectional"))
    )
    (net (code "23") (name "/MEZZ_IO8") (class "Default")
      (node (ref "IC1") (pin "10") (pinfunction "P10_10") (pintype "bidirectional"))
      (node (ref "J13") (pin "11") (pinfunction "11_11") (pintype "bidirectional"))
    )
    (net (code "24") (name "/MEZZ_IO9") (class "Default")
      (node (ref "IC1") (pin "11") (pinfunction "P11_11") (pintype "bidirectional"))
      (node (ref "J13") (pin "12") (pinfunction "12_12") (pintype "bidirectional"))
    )
    (net (code "25") (name "/MEZZ_IO10") (class "Default")
      (node (ref "IC1") (pin "12") (pinfunction "P12_12") (pintype "bidirectional"))
      (node (ref "J13") (pin "13") (pinfunction "13_13") (pintype "bidirectional"))
    )
    (net (code "26") (name "/MEZZ_IO11") (class "Default")
      (node (ref "IC1") (pin "13") (pinfunction "P13_13") (pintype "bidirectional"))
      (node (ref "J13") (pin "14") (pinfunction "14_14") (pintype "bidirectional"))
    )
    (net (code "27") (name "/MEZZ_IO12") (class "Default")
      (node (ref "IC1") (pin "14") (pinfunction "P14_14") (pintype "bidirectional"))
      (node (ref "J13") (pin "15") (pinfunction "15_15") (pintype "bidirectional"))
    )
    (net (code "28") (name "/MEZZ_IO13") (class "Default")
      (node (ref "IC1") (pin "15") (pinfunction "P15_15") (pintype "bidirectional"))
      (node (ref "J13") (pin "16") (pinfunction "16_16") (pintype "bidirectional"))
    )
    (net (code "29") (name "/MEZZ_IO14") (class "Default")
      (node (ref "IC1") (pin "16") (pinfunction "P16_16") (pintype "bidirectional"))
      (node (ref "J13") (pin "17") (pinfunction "17_17") (pintype "bidirectional"))
    )
    (net (code "30") (name "/MEZZ_IO15") (class "Default")
      (node (ref "IC1") (pin "17") (pinfunction "P17_17") (pintype "bidirectional"))
      (node (ref "J13") (pin "18") (pinfunction "18_18") (pintype "bidirectional"))
    )
    (net (code "31") (name "/RF1_IN") (class "Default")
      (node (ref "J17") (pin "1") (pinfunction "1_1") (pintype "bidirectional"))
    )
    (net (code "32") (name "/RF1_OUT") (class "Default")
      (node (ref "J8") (pin "1") (pinfunction "1_1") (pintype "bidirectional"))
    )
    (net (code "33") (name "/RF2_IN") (class "Default")
      (node (ref "J20") (pin "1") (pinfunction "1_1") (pintype "bidirectional"))
    )
    (net (code "34") (name "/RF2_OUT") (class "Default")
      (node (ref "J11") (pin "1") (pinfunction "1_1") (pintype "bidirectional"))
    )
    (net (code "35") (name "/SCL") (class "Default")
      (node (ref "IC1") (pin "19") (pinfunction "SCL_19") (pintype "input"))
      (node (ref "IC3") (pin "1") (pinfunction "SCL_1") (pintype "input"))
      (node (ref "IC4") (pin "2") (pinfunction "SCL_2") (pintype "input"))
      (node (ref "IC5") (pin "19") (pinfunction "SCL_19") (pintype "input"))
      (node (ref "J13") (pin "21") (pinfunction "21_21") (pintype "bidirectional"))
    )
    (net (code "36") (name "/SDA") (class "Default")
      (node (ref "IC1") (pin "20") (pinfunction "SDA_20") (pintype "bidirectional"))
      (node (ref "IC3") (pin "3") (pinfunction "SDA_3") (pintype "bidirectional"))
      (node (ref "IC4") (pin "1") (pinfunction "SDA_1") (pintype "bidirectional"))
      (node (ref "IC5") (pin "20") (pinfunction "SDA_20") (pintype "bidirectional"))
      (node (ref "J13") (pin "22") (pinfunction "22_22") (pintype "bidirectional"))
    )
    (net (code "37") (name "/SW1") (class "Default")
      (node (ref "IC5") (pin "1") (pinfunction "P00_1") (pintype "bidirectional"))
      (node (ref "R48") (pin "1") (pinfunction "1_1") (pintype "passive"))
      (node (ref "T5") (pin "1") (pinfunction "G_1") (pintype "passive"))
    )
    (net (code "38") (name "/SW2") (class "Default")
      (node (ref "IC5") (pin "2") (pinfunction "P01_2") (pintype "bidirectional"))
      (node (ref "R49") (pin "1") (pinfunction "1_1") (pintype "passive"))
      (node (ref "T6") (pin "1") (pinfunction "G_1") (pintype "passive"))
    )
    (net (code "39") (name "/SW3") (class "Default")
      (node (ref "IC5") (pin "3") (pinfunction "P02_3") (pintype "bidirectional"))
      (node (ref "R50") (pin "1") (pinfunction "1_1") (pintype "passive"))
      (node (ref "T7") (pin "1") (pinfunction "G_1") (pintype "passive"))
    )
    (net (code "40") (name "/SW4") (class "Default")
      (node (ref "IC5") (pin "4") (pinfunction "P03_4") (pintype "bidirectional"))
      (node (ref "R51") (pin "1") (pinfunction "1_1") (pintype "passive"))
      (node (ref "T8") (pin "1") (pinfunction "G_1") (pintype "passive"))
    )
    (net (code "41") (name "/SW5") (class "Default")
      (node (ref "IC5") (pin "5") (pinfunction "P04_5") (pintype "bidirectional"))
      (node (ref "R52") (pin "1") (pinfunction "1_1") (pintype "passive"))
      (node (ref "T9") (pin "1") (pinfunction "G_1") (pintype "passive"))
    )
    (net (code "42") (name "/SW6") (class "Default")
      (node (ref "IC5") (pin "6") (pinfunction "P05_6") (pintype "bidirectional"))
      (node (ref "R53") (pin "1") (pinfunction "1_1") (pintype "passive"))
      (node (ref "T10") (pin "1") (pinfunction "G_1") (pintype "passive"))
    )
    (net (code "43") (name "/SW7") (class "Default")
      (node (ref "IC5") (pin "7") (pinfunction "P06_7") (pintype "bidirectional"))
      (node (ref "R54") (pin "1") (pinfunction "1_1") (pintype "passive"))
      (node (ref "T11") (pin "1") (pinfunction "G_1") (pintype "passive"))
    )
    (net (code "44") (name "/SW8") (class "Default")
      (node (ref "IC5") (pin "8") (pinfunction "P07_8") (pintype "bidirectional"))
      (node (ref "R55") (pin "1") (pinfunction "1_1") (pintype "passive"))
      (node (ref "T12") (pin "1") (pinfunction "G_1") (pintype "passive"))
    )
    (net (code "45") (name "/SW9") (class "Default")
      (node (ref "IC5") (pin "10") (pinfunction "P10_10") (pintype "bidirectional"))
      (node (ref "R44") (pin "1") (pinfunction "1_1") (pintype "passive"))
      (node (ref "T1") (pin "1") (pinfunction "G_1") (pintype "passive"))
    )
    (net (code "46") (name "/SW10") (class "Default")
      (node (ref "IC5") (pin "11") (pinfunction "P11_11") (pintype "bidirectional"))
      (node (ref "R45") (pin "1") (pinfunction "1_1") (pintype "passive"))
      (node (ref "T2") (pin "1") (pinfunction "G_1") (pintype "passive"))
    )
    (net (code "47") (name "/VCM") (class "Default")
      (node (ref "J13") (pin "33") (pinfunction "33_33") (pintype "bidirectional"))
    )
    (net (code "48") (name "GND") (class "Default")
      (node (ref "C10") (pin "1") (pinfunction "1_1") (pintype "passive"))
      (node (ref "C11") (pin "1") (pinfunction "1_1") (pintype "passive"))
      (node (ref "C12") (pin "1") (pinfunction "1_1") (pintype "passive"))
      (node (ref "C25") (pin "1") (pinfunction "1_1") (pintype "passive"))
      (node (ref "C26") (pin "1") (pinfunction "1_1") (pintype "passive"))
      (node (ref "C27") (pin "1") (pinfunction "1_1") (pintype "passive"))
      (node (ref "IC1") (pin "18") (pinfunction "A0_18") (pintype "bidirectional"))
      (node (ref "IC1") (pin "23") (pinfunction "A1_23") (pintype "bidirectional"))
      (node (ref "IC1") (pin "9") (pinfunction "GND_9") (pintype "power_in"))
      (node (ref "IC3") (pin "2") (pinfunction "VSS_2") (pintype "power_in"))
      (node (ref "IC4") (pin "4") (pinfunction "GND_4") (pintype "power_in"))
      (node (ref "IC4") (pin "5") (pinfunction "A2_5") (pintype "input"))
      (node (ref "IC4") (pin "6") (pinfunction "A1_6") (pintype "input"))
      (node (ref "IC4") (pin "7") (pinfunction "A0_7") (pintype "input"))
      (node (ref "IC5") (pin "23") (pinfunction "A1_23") (pintype "bidirectional"))
      (node (ref "IC5") (pin "9") (pinfunction "GND_9") (pintype "power_in"))
      (node (ref "IC6") (pin "3") (pinfunction "GND_3") (pintype "power_in"))
      (node (ref "IC6") (pin "6") (pinfunction "GND_6") (pintype "power_in"))
      (node (ref "IC6") (pin "9") (pinfunction "EP_9") (pintype "power_in"))
      (node (ref "IC7") (pin "1") (pinfunction "GND_1") (pintype "power_in"))
      (node (ref "J10") (pin "2") (pinfunction "2_2") (pintype "bidirectional"))
      (node (ref "J11") (pin "2") (pinfunction "2_2") (pintype "bidirectional"))
      (node (ref "J12") (pin "2") (pinfunction "2_2") (pintype "bidirectional"))
      (node (ref "J13") (pin "1") (pinfunction "1_1") (pintype "bidirectional"))
      (node (ref "J13") (pin "2") (pinfunction "2_2") (pintype "bidirectional"))
      (node (ref "J13") (pin "23") (pinfunction "23_23") (pintype "bidirectional"))
      (node (ref "J13") (pin "24") (pinfunction "24_24") (pintype "bidirectional"))
      (node (ref "J13") (pin "29") (pinfunction "29_29") (pintype "bidirectional"))
      (node (ref "J13") (pin "30") (pinfunction "30_30") (pintype "bidirectional"))
      (node (ref "J13") (pin "35") (pinfunction "35_35") (pintype "bidirectional"))
      (node (ref "J13") (pin "36") (pinfunction "36_36") (pintype "bidirectional"))
      (node (ref "J16") (pin "2") (pinfunction "2_2") (pintype "bidirectional"))
      (node (ref "J17") (pin "2") (pinfunction "2_2") (pintype "bidirectional"))
      (node (ref "J18") (pin "2") (pinfunction "2_2") (pintype "bidirectional"))
      (node (ref "J19") (pin "2") (pinfunction "2_2") (pintype "bidirectional"))
      (node (ref "J20") (pin "2") (pinfunction "2_2") (pintype "bidirectional"))
      (node (ref "J21") (pin "2") (pinfunction "2_2") (pintype "bidirectional"))
      (node (ref "J22") (pin "2") (pinfunction "2_2") (pintype "bidirectional"))
      (node (ref "J23") (pin "2") (pinfunction "2_2") (pintype "bidirectional"))
      (node (ref "J7") (pin "2") (pinfunction "2_2") (pintype "bidirectional"))
      (node (ref "J8") (pin "2") (pinfunction "2_2") (pintype "bidirectional"))
      (node (ref "J9") (pin "2") (pinfunction "2_2") (pintype "bidirectional"))
      (node (ref "R3") (pin "1") (pinfunction "1_1") (pintype "passive"))
      (node (ref "R4") (pin "1") (pinfunction "1_1") (pintype "passive"))
      (node (ref "R44") (pin "2") (pinfunction "2_2") (pintype "passive"))
      (node (ref "R45") (pin "2") (pinfunction "2_2") (pintype "passive"))
      (node (ref "R48") (pin "2") (pinfunction "2_2") (pintype "passive"))
      (node (ref "R49") (pin "2") (pinfunction "2_2") (pintype "passive"))
      (node (ref "R50") (pin "2") (pinfunction "2_2") (pintype "passive"))
      (node (ref "R51") (pin "2") (pinfunction "2_2") (pintype "passive"))
      (node (ref "R52") (pin "2") (pinfunction "2_2") (pintype "passive"))
      (node (ref "R53") (pin "2") (pinfunction "2_2") (pintype "passive"))
      (node (ref "R54") (pin "2") (pinfunction "2_2") (pintype "passive"))
      (node (ref "R55") (pin "2") (pinfunction "2_2") (pintype "passive"))
      (node (ref "SW1") (pin "3") (pinfunction "3_3") (pintype "passive"))
      (node (ref "SW1") (pin "4") (pinfunction "4_4") (pintype "passive"))
      (node (ref "SW2") (pin "10") (pinfunction "10_10") (pintype "passive"))
      (node (ref "SW2") (pin "11") (pinfunction "11_11") (pintype "passive"))
      (node (ref "SW2") (pin "12") (pinfunction "12_12") (pintype "passive"))
      (node (ref "SW2") (pin "13") (pinfunction "13_13") (pintype "passive"))
      (node (ref "SW2") (pin "14") (pinfunction "14_14") (pintype "passive"))
      (node (ref "SW2") (pin "15") (pinfunction "15_15") (pintype "passive"))
      (node (ref "SW2") (pin "16") (pinfunction "16_16") (pintype "passive"))
      (node (ref "SW2") (pin "9") (pinfunction "9_9") (pintype "passive"))
      (node (ref "T10") (pin "2") (pinfunction "S_2") (pintype "passive"))
      (node (ref "T11") (pin "2") (pinfunction "S_2") (pintype "passive"))
      (node (ref "T12") (pin "2") (pinfunction "S_2") (pintype "passive"))
      (node (ref "T3") (pin "2") (pinfunction "S_2") (pintype "passive"))
      (node (ref "T4") (pin "2") (pinfunction "S_2") (pintype "passive"))
      (node (ref "T5") (pin "2") (pinfunction "S_2") (pintype "passive"))
      (node (ref "T6") (pin "2") (pinfunction "S_2") (pintype "passive"))
      (node (ref "T7") (pin "2") (pinfunction "S_2") (pintype "passive"))
      (node (ref "T8") (pin "2") (pinfunction "S_2") (pintype "passive"))
      (node (ref "T9") (pin "2") (pinfunction "S_2") (pintype "passive"))
    )
    (net (code "49") (name "N5V0A") (class "Default")
      (node (ref "C27") (pin "2") (pinfunction "2_2") (pintype "passive"))
      (node (ref "IC7") (pin "5") (pinfunction "VOUT_5") (pintype "power_in"))
    )
    (net (code "50") (name "N6V0A") (class "Default")
      (node (ref "C26") (pin "2") (pinfunction "2_2") (pintype "passive"))
      (node (ref "IC7") (pin "2") (pinfunction "VIN_2") (pintype "input"))
      (node (ref "IC7") (pin "3") (pinfunction "EN_3") (pintype "input"))
      (node (ref "J13") (pin "31") (pinfunction "31_31") (pintype "bidirectional"))
      (node (ref "R36") (pin "1") (pinfunction "1_1") (pintype "passive"))
      (node (ref "R38") (pin "1") (pinfunction "1_1") (pintype "passive"))
      (node (ref "R46") (pin "2") (pinfunction "2_2") (pintype "passive"))
      (node (ref "R47") (pin "2") (pinfunction "2_2") (pintype "passive"))
      (node (ref "R7") (pin "2") (pinfunction "2_2") (pintype "passive"))
      (node (ref "TP4") (pin "1") (pinfunction "1_1") (pintype "bidirectional"))
    )
    (net (code "51") (name "N12V0A") (class "Default")
      (node (ref "J13") (pin "25") (pinfunction "25_25") (pintype "bidirectional"))
      (node (ref "R24") (pin "1") (pinfunction "1_1") (pintype "passive"))
      (node (ref "R26") (pin "1") (pinfunction "1_1") (pintype "passive"))
      (node (ref "R8") (pin "2") (pinfunction "2_2") (pintype "passive"))
      (node (ref "TP2") (pin "1") (pinfunction "1_1") (pintype "bidirectional"))
    )
    (net (code "52") (name "Net-(R18-Pad2)") (class "Default")
      (node (ref "R18") (pin "2") (pinfunction "2_2") (pintype "passive"))
      (node (ref "R19") (pin "1") (pinfunction "1_1") (pintype "passive"))
    )
    (net (code "53") (name "Net-(R19-Pad2)") (class "Default")
      (node (ref "R19") (pin "2") (pinfunction "2_2") (pintype "passive"))
      (node (ref "R20") (pin "1") (pinfunction "1_1") (pintype "passive"))
    )
    (net (code "54") (name "Net-(R21-Pad2)") (class "Default")
      (node (ref "R21") (pin "2") (pinfunction "2_2") (pintype "passive"))
      (node (ref "R22") (pin "1") (pinfunction "1_1") (pintype "passive"))
    )
    (net (code "55") (name "Net-(R22-Pad2)") (class "Default")
      (node (ref "R22") (pin "2") (pinfunction "2_2") (pintype "passive"))
      (node (ref "R23") (pin "1") (pinfunction "1_1") (pintype "passive"))
    )
    (net (code "56") (name "Net-(R24-Pad2)") (class "Default")
      (node (ref "R24") (pin "2") (pinfunction "2_2") (pintype "passive"))
      (node (ref "R25") (pin "1") (pinfunction "1_1") (pintype "passive"))
    )
    (net (code "57") (name "Net-(R26-Pad2)") (class "Default")
      (node (ref "R26") (pin "2") (pinfunction "2_2") (pintype "passive"))
      (node (ref "R27") (pin "1") (pinfunction "1_1") (pintype "passive"))
    )
    (net (code "58") (name "Net-(R28-Pad2)") (class "Default")
      (node (ref "R28") (pin "2") (pinfunction "2_2") (pintype "passive"))
      (node (ref "R29") (pin "1") (pinfunction "1_1") (pintype "passive"))
    )
    (net (code "59") (name "Net-(R29-Pad2)") (class "Default")
      (node (ref "R29") (pin "2") (pinfunction "2_2") (pintype "passive"))
      (node (ref "R30") (pin "1") (pinfunction "1_1") (pintype "passive"))
    )
    (net (code "60") (name "Net-(R30-Pad2)") (class "Default")
      (node (ref "R30") (pin "2") (pinfunction "2_2") (pintype "passive"))
      (node (ref "R31") (pin "1") (pinfunction "1_1") (pintype "passive"))
    )
    (net (code "61") (name "Net-(R32-Pad2)") (class "Default")
      (node (ref "R32") (pin "2") (pinfunction "2_2") (pintype "passive"))
      (node (ref "R33") (pin "1") (pinfunction "1_1") (pintype "passive"))
    )
    (net (code "62") (name "Net-(R33-Pad2)") (class "Default")
      (node (ref "R33") (pin "2") (pinfunction "2_2") (pintype "passive"))
      (node (ref "R34") (pin "1") (pinfunction "1_1") (pintype "passive"))
    )
    (net (code "63") (name "Net-(R34-Pad2)") (class "Default")
      (node (ref "R34") (pin "2") (pinfunction "2_2") (pintype "passive"))
      (node (ref "R35") (pin "1") (pinfunction "1_1") (pintype "passive"))
    )
    (net (code "64") (name "Net-(R36-Pad2)") (class "Default")
      (node (ref "R36") (pin "2") (pinfunction "2_2") (pintype "passive"))
      (node (ref "R37") (pin "1") (pinfunction "1_1") (pintype "passive"))
    )
    (net (code "65") (name "Net-(R38-Pad2)") (class "Default")
      (node (ref "R38") (pin "2") (pinfunction "2_2") (pintype "passive"))
      (node (ref "R39") (pin "1") (pinfunction "1_1") (pintype "passive"))
    )
    (net (code "66") (name "Net-(R40-Pad2)") (class "Default")
      (node (ref "R40") (pin "2") (pinfunction "2_2") (pintype "passive"))
      (node (ref "R41") (pin "1") (pinfunction "1_1") (pintype "passive"))
    )
    (net (code "67") (name "Net-(R42-Pad2)") (class "Default")
      (node (ref "R42") (pin "2") (pinfunction "2_2") (pintype "passive"))
      (node (ref "R43") (pin "1") (pinfunction "1_1") (pintype "passive"))
    )
    (net (code "68") (name "Net-(T1-D)") (class "Default")
      (node (ref "R46") (pin "1") (pinfunction "1_1") (pintype "passive"))
      (node (ref "T1") (pin "3") (pinfunction "D_3") (pintype "passive"))
      (node (ref "T3") (pin "1") (pinfunction "G_1") (pintype "passive"))
    )
    (net (code "69") (name "Net-(T2-D)") (class "Default")
      (node (ref "R47") (pin "1") (pinfunction "1_1") (pintype "passive"))
      (node (ref "T2") (pin "3") (pinfunction "D_3") (pintype "passive"))
      (node (ref "T4") (pin "1") (pinfunction "G_1") (pintype "passive"))
    )
    (net (code "70") (name "Net-(T3-D)") (class "Default")
      (node (ref "R37") (pin "2") (pinfunction "2_2") (pintype "passive"))
      (node (ref "SW2") (pin "5") (pinfunction "5_5") (pintype "passive"))
      (node (ref "T3") (pin "3") (pinfunction "D_3") (pintype "passive"))
    )
    (net (code "71") (name "Net-(T4-D)") (class "Default")
      (node (ref "R39") (pin "2") (pinfunction "2_2") (pintype "passive"))
      (node (ref "SW2") (pin "6") (pinfunction "6_6") (pintype "passive"))
      (node (ref "T4") (pin "3") (pinfunction "D_3") (pintype "passive"))
    )
    (net (code "72") (name "Net-(T5-D)") (class "Default")
      (node (ref "R43") (pin "2") (pinfunction "2_2") (pintype "passive"))
      (node (ref "SW2") (pin "8") (pinfunction "8_8") (pintype "passive"))
      (node (ref "T5") (pin "3") (pinfunction "D_3") (pintype "passive"))
    )
    (net (code "73") (name "Net-(T6-D)") (class "Default")
      (node (ref "R41") (pin "2") (pinfunction "2_2") (pintype "passive"))
      (node (ref "SW2") (pin "7") (pinfunction "7_7") (pintype "passive"))
      (node (ref "T6") (pin "3") (pinfunction "D_3") (pintype "passive"))
    )
    (net (code "74") (name "Net-(T7-D)") (class "Default")
      (node (ref "R35") (pin "2") (pinfunction "2_2") (pintype "passive"))
      (node (ref "SW2") (pin "4") (pinfunction "4_4") (pintype "passive"))
      (node (ref "T7") (pin "3") (pinfunction "D_3") (pintype "passive"))
    )
    (net (code "75") (name "Net-(T8-D)") (class "Default")
      (node (ref "R31") (pin "2") (pinfunction "2_2") (pintype "passive"))
      (node (ref "SW2") (pin "3") (pinfunction "3_3") (pintype "passive"))
      (node (ref "T8") (pin "3") (pinfunction "D_3") (pintype "passive"))
    )
    (net (code "76") (name "Net-(T9-D)") (class "Default")
      (node (ref "R27") (pin "2") (pinfunction "2_2") (pintype "passive"))
      (node (ref "SW2") (pin "2") (pinfunction "2_2") (pintype "passive"))
      (node (ref "T9") (pin "3") (pinfunction "D_3") (pintype "passive"))
    )
    (net (code "77") (name "Net-(T10-D)") (class "Default")
      (node (ref "R25") (pin "2") (pinfunction "2_2") (pintype "passive"))
      (node (ref "SW2") (pin "1") (pinfunction "1_1") (pintype "passive"))
      (node (ref "T10") (pin "3") (pinfunction "D_3") (pintype "passive"))
    )
    (net (code "78") (name "Net-(T11-D)") (class "Default")
      (node (ref "R23") (pin "2") (pinfunction "2_2") (pintype "passive"))
      (node (ref "SW1") (pin "2") (pinfunction "2_2") (pintype "passive"))
      (node (ref "T11") (pin "3") (pinfunction "D_3") (pintype "passive"))
    )
    (net (code "79") (name "Net-(T12-D)") (class "Default")
      (node (ref "R20") (pin "2") (pinfunction "2_2") (pintype "passive"))
      (node (ref "SW1") (pin "1") (pinfunction "1_1") (pintype "passive"))
      (node (ref "T12") (pin "3") (pinfunction "D_3") (pintype "passive"))
    )
    (net (code "80") (name "P3V3") (class "Default")
      (node (ref "C10") (pin "2") (pinfunction "2_2") (pintype "passive"))
      (node (ref "C12") (pin "2") (pinfunction "2_2") (pintype "passive"))
      (node (ref "IC1") (pin "21") (pinfunction "VCC_21") (pintype "power_in"))
      (node (ref "IC1") (pin "24") (pinfunction "~{RESET}_24") (pintype "input"))
      (node (ref "IC3") (pin "4") (pinfunction "VCC_4") (pintype "power_in"))
      (node (ref "IC4") (pin "8") (pinfunction "+VS_8") (pintype "power_in"))
      (node (ref "IC5") (pin "18") (pinfunction "A0_18") (pintype "bidirectional"))
      (node (ref "IC5") (pin "21") (pinfunction "VCC_21") (pintype "power_in"))
      (node (ref "IC5") (pin "24") (pinfunction "~{RESET}_24") (pintype "input"))
      (node (ref "J13") (pin "19") (pinfunction "19_19") (pintype "bidirectional"))
      (node (ref "R40") (pin "1") (pinfunction "1_1") (pintype "passive"))
      (node (ref "R42") (pin "1") (pinfunction "1_1") (pintype "passive"))
      (node (ref "R5") (pin "1") (pinfunction "1_1") (pintype "passive"))
      (node (ref "R6") (pin "1") (pinfunction "1_1") (pintype "passive"))
      (node (ref "T1") (pin "2") (pinfunction "S_2") (pintype "passive"))
      (node (ref "T2") (pin "2") (pinfunction "S_2") (pintype "passive"))
      (node (ref "TP5") (pin "1") (pinfunction "1_1") (pintype "bidirectional"))
    )
    (net (code "81") (name "P5V0A") (class "Default")
      (node (ref "C25") (pin "2") (pinfunction "2_2") (pintype "passive"))
      (node (ref "IC6") (pin "1") (pinfunction "VOUT_1") (pintype "power_in"))
      (node (ref "IC6") (pin "2") (pinfunction "SENS_2") (pintype "input"))
    )
    (net (code "82") (name "P6V0A") (class "Default")
      (node (ref "C11") (pin "2") (pinfunction "2_2") (pintype "passive"))
      (node (ref "IC6") (pin "5") (pinfunction "EN/UVLO_5") (pintype "input"))
      (node (ref "IC6") (pin "8") (pinfunction "VIN_8") (pintype "input"))
      (node (ref "J13") (pin "32") (pinfunction "32_32") (pintype "bidirectional"))
      (node (ref "J13") (pin "34") (pinfunction "34_34") (pintype "bidirectional"))
      (node (ref "R2") (pin "2") (pinfunction "2_2") (pintype "passive"))
      (node (ref "R28") (pin "1") (pinfunction "1_1") (pintype "passive"))
      (node (ref "R32") (pin "1") (pinfunction "1_1") (pintype "passive"))
      (node (ref "TP3") (pin "1") (pinfunction "1_1") (pintype "bidirectional"))
    )
    (net (code "83") (name "P12V0A") (class "Default")
      (node (ref "J13") (pin "26") (pinfunction "26_26") (pintype "bidirectional"))
      (node (ref "R1") (pin "2") (pinfunction "2_2") (pintype "passive"))
      (node (ref "R18") (pin "1") (pinfunction "1_1") (pintype "passive"))
      (node (ref "R21") (pin "1") (pinfunction "1_1") (pintype "passive"))
      (node (ref "TP1") (pin "1") (pinfunction "1_1") (pintype "bidirectional"))
    )
    (net (code "84") (name "unconnected-(IC1-~{INT}-Pad22)") (class "Default")
      (node (ref "IC1") (pin "22") (pinfunction "~{INT}_22") (pintype "output"))
    )
    (net (code "85") (name "unconnected-(IC3-NC-Pad5)") (class "Default")
      (node (ref "IC3") (pin "5") (pinfunction "NC_5") (pintype "passive"))
    )
    (net (code "86") (name "unconnected-(IC4-O.S.-Pad3)") (class "Default")
      (node (ref "IC4") (pin "3") (pinfunction "O.S._3") (pintype "output"))
    )
    (net (code "87") (name "unconnected-(IC5-P12-Pad12)") (class "Default")
      (node (ref "IC5") (pin "12") (pinfunction "P12_12") (pintype "bidirectional"))
    )
    (net (code "88") (name "unconnected-(IC5-P13-Pad13)") (class "Default")
      (node (ref "IC5") (pin "13") (pinfunction "P13_13") (pintype "bidirectional"))
    )
    (net (code "89") (name "unconnected-(IC5-P14-Pad14)") (class "Default")
      (node (ref "IC5") (pin "14") (pinfunction "P14_14") (pintype "bidirectional"))
    )
    (net (code "90") (name "unconnected-(IC5-P15-Pad15)") (class "Default")
      (node (ref "IC5") (pin "15") (pinfunction "P15_15") (pintype "bidirectional"))
    )
    (net (code "91") (name "unconnected-(IC5-P16-Pad16)") (class "Default")
      (node (ref "IC5") (pin "16") (pinfunction "P16_16") (pintype "bidirectional"))
    )
    (net (code "92") (name "unconnected-(IC5-P17-Pad17)") (class "Default")
      (node (ref "IC5") (pin "17") (pinfunction "P17_17") (pintype "bidirectional"))
    )
    (net (code "93") (name "unconnected-(IC5-~{INT}-Pad22)") (class "Default")
      (node (ref "IC5") (pin "22") (pinfunction "~{INT}_22") (pintype "output"))
    )
    (net (code "94") (name "unconnected-(IC6-NC-Pad4)") (class "Default")
      (node (ref "IC6") (pin "4") (pinfunction "NC_4") (pintype "passive"))
    )
    (net (code "95") (name "unconnected-(IC6-PG-Pad7)") (class "Default")
      (node (ref "IC6") (pin "7") (pinfunction "PG_7") (pintype "output"))
    )
    (net (code "96") (name "unconnected-(IC7-NC-Pad4)") (class "Default")
      (node (ref "IC7") (pin "4") (pinfunction "NC_4") (pintype "passive"))
    )
    (net (code "97") (name "unconnected-(J13-Pad20)") (class "Default")
      (node (ref "J13") (pin "20") (pinfunction "20_20") (pintype "bidirectional"))
    )
    (net (code "98") (name "unconnected-(J13-Pad27)") (class "Default")
      (node (ref "J13") (pin "27") (pinfunction "27_27") (pintype "bidirectional"))
    )
    (net (code "99") (name "unconnected-(J13-Pad28)") (class "Default")
      (node (ref "J13") (pin "28") (pinfunction "28_28") (pintype "bidirectional"))
    )
  )
)
